# phaser.net
KiCad netlist of a schematic drawn in EAGLE
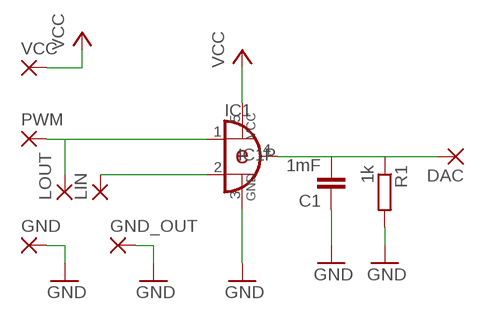
[diagram p0: schematic, sheet 1]

(export (version "E")
  (design (tool "Eeschema 10.0.6"))
  (components
    (comp (ref "C1")
      (value "1mF")
      (footprint "eagle-import:C0805")
      (libsource (lib "eagle-import") (part "C-EUC0805"))
    )
    (comp (ref "DAC")
      (value "SMD2")
      (footprint "eagle-import:SMD1,27-2,54")
      (libsource (lib "eagle-import") (part "SMD2"))
    )
    (comp (ref "GND")
      (value "SMD2")
      (footprint "eagle-import:SMD1,27-2,54")
      (libsource (lib "eagle-import") (part "SMD2"))
    )
    (comp (ref "GND_OUT")
      (value "SMD2")
      (footprint "eagle-import:SMD1,27-2,54")
      (libsource (lib "eagle-import") (part "SMD2"))
    )
    (comp (ref "IC1")
      (value "74AHC1G86DCK")
      (footprint "eagle-import:SC70-5")
      (libsource (lib "eagle-import") (part "741G86DCKAHC"))
    )
    (comp (ref "LIN")
      (value "SMD2")
      (footprint "eagle-import:SMD1,27-2,54")
      (libsource (lib "eagle-import") (part "SMD2"))
    )
    (comp (ref "LOUT")
      (value "SMD2")
      (footprint "eagle-import:SMD1,27-2,54")
      (libsource (lib "eagle-import") (part "SMD2"))
    )
    (comp (ref "PWM")
      (value "SMD2")
      (footprint "eagle-import:SMD1,27-2,54")
      (libsource (lib "eagle-import") (part "SMD2"))
    )
    (comp (ref "R1")
      (value "1k")
      (footprint "eagle-import:R0805")
      (libsource (lib "eagle-import") (part "R-EU_R0805"))
    )
    (comp (ref "VCC")
      (value "SMD2")
      (footprint "eagle-import:SMD1,27-2,54")
      (libsource (lib "eagle-import") (part "SMD2"))
    )
  )
  (nets
    (net (code "1") (name "GND") (class "Default")
      (node (ref "C1") (pin "1") (pinfunction "1_1") (pintype "passive"))
      (node (ref "GND") (pin "1") (pinfunction "P_1") (pintype "passive"))
      (node (ref "GND_OUT") (pin "1") (pinfunction "P_1") (pintype "passive"))
      (node (ref "IC1") (pin "3") (pinfunction "GND_3") (pintype "power_in"))
      (node (ref "R1") (pin "2") (pinfunction "2_2") (pintype "passive"))
    )
    (net (code "2") (name "Net-(DAC-P)") (class "Default")
      (node (ref "C1") (pin "2") (pinfunction "2_2") (pintype "passive"))
      (node (ref "DAC") (pin "1") (pinfunction "P_1") (pintype "passive"))
      (node (ref "IC1") (pin "4") (pinfunction "O_4") (pintype "output"))
      (node (ref "R1") (pin "1") (pinfunction "1_1") (pintype "passive"))
    )
    (net (code "3") (name "Net-(IC1A-I0)") (class "Default")
      (node (ref "IC1") (pin "1") (pinfunction "I0_1") (pintype "input"))
      (node (ref "LOUT") (pin "1") (pinfunction "P_1") (pintype "passive"))
      (node (ref "PWM") (pin "1") (pinfunction "P_1") (pintype "passive"))
    )
    (net (code "4") (name "Net-(IC1A-I1)") (class "Default")
      (node (ref "IC1") (pin "2") (pinfunction "I1_2") (pintype "input"))
      (node (ref "LIN") (pin "1") (pinfunction "P_1") (pintype "passive"))
    )
    (net (code "5") (name "VCC") (class "Default")
      (node (ref "IC1") (pin "5") (pinfunction "VCC_5") (pintype "power_in"))
      (node (ref "VCC") (pin "1") (pinfunction "P_1") (pintype "passive"))
    )
  )
)
